# design.net
KiCad netlist of a schematic drawn in EasyEDA Pro
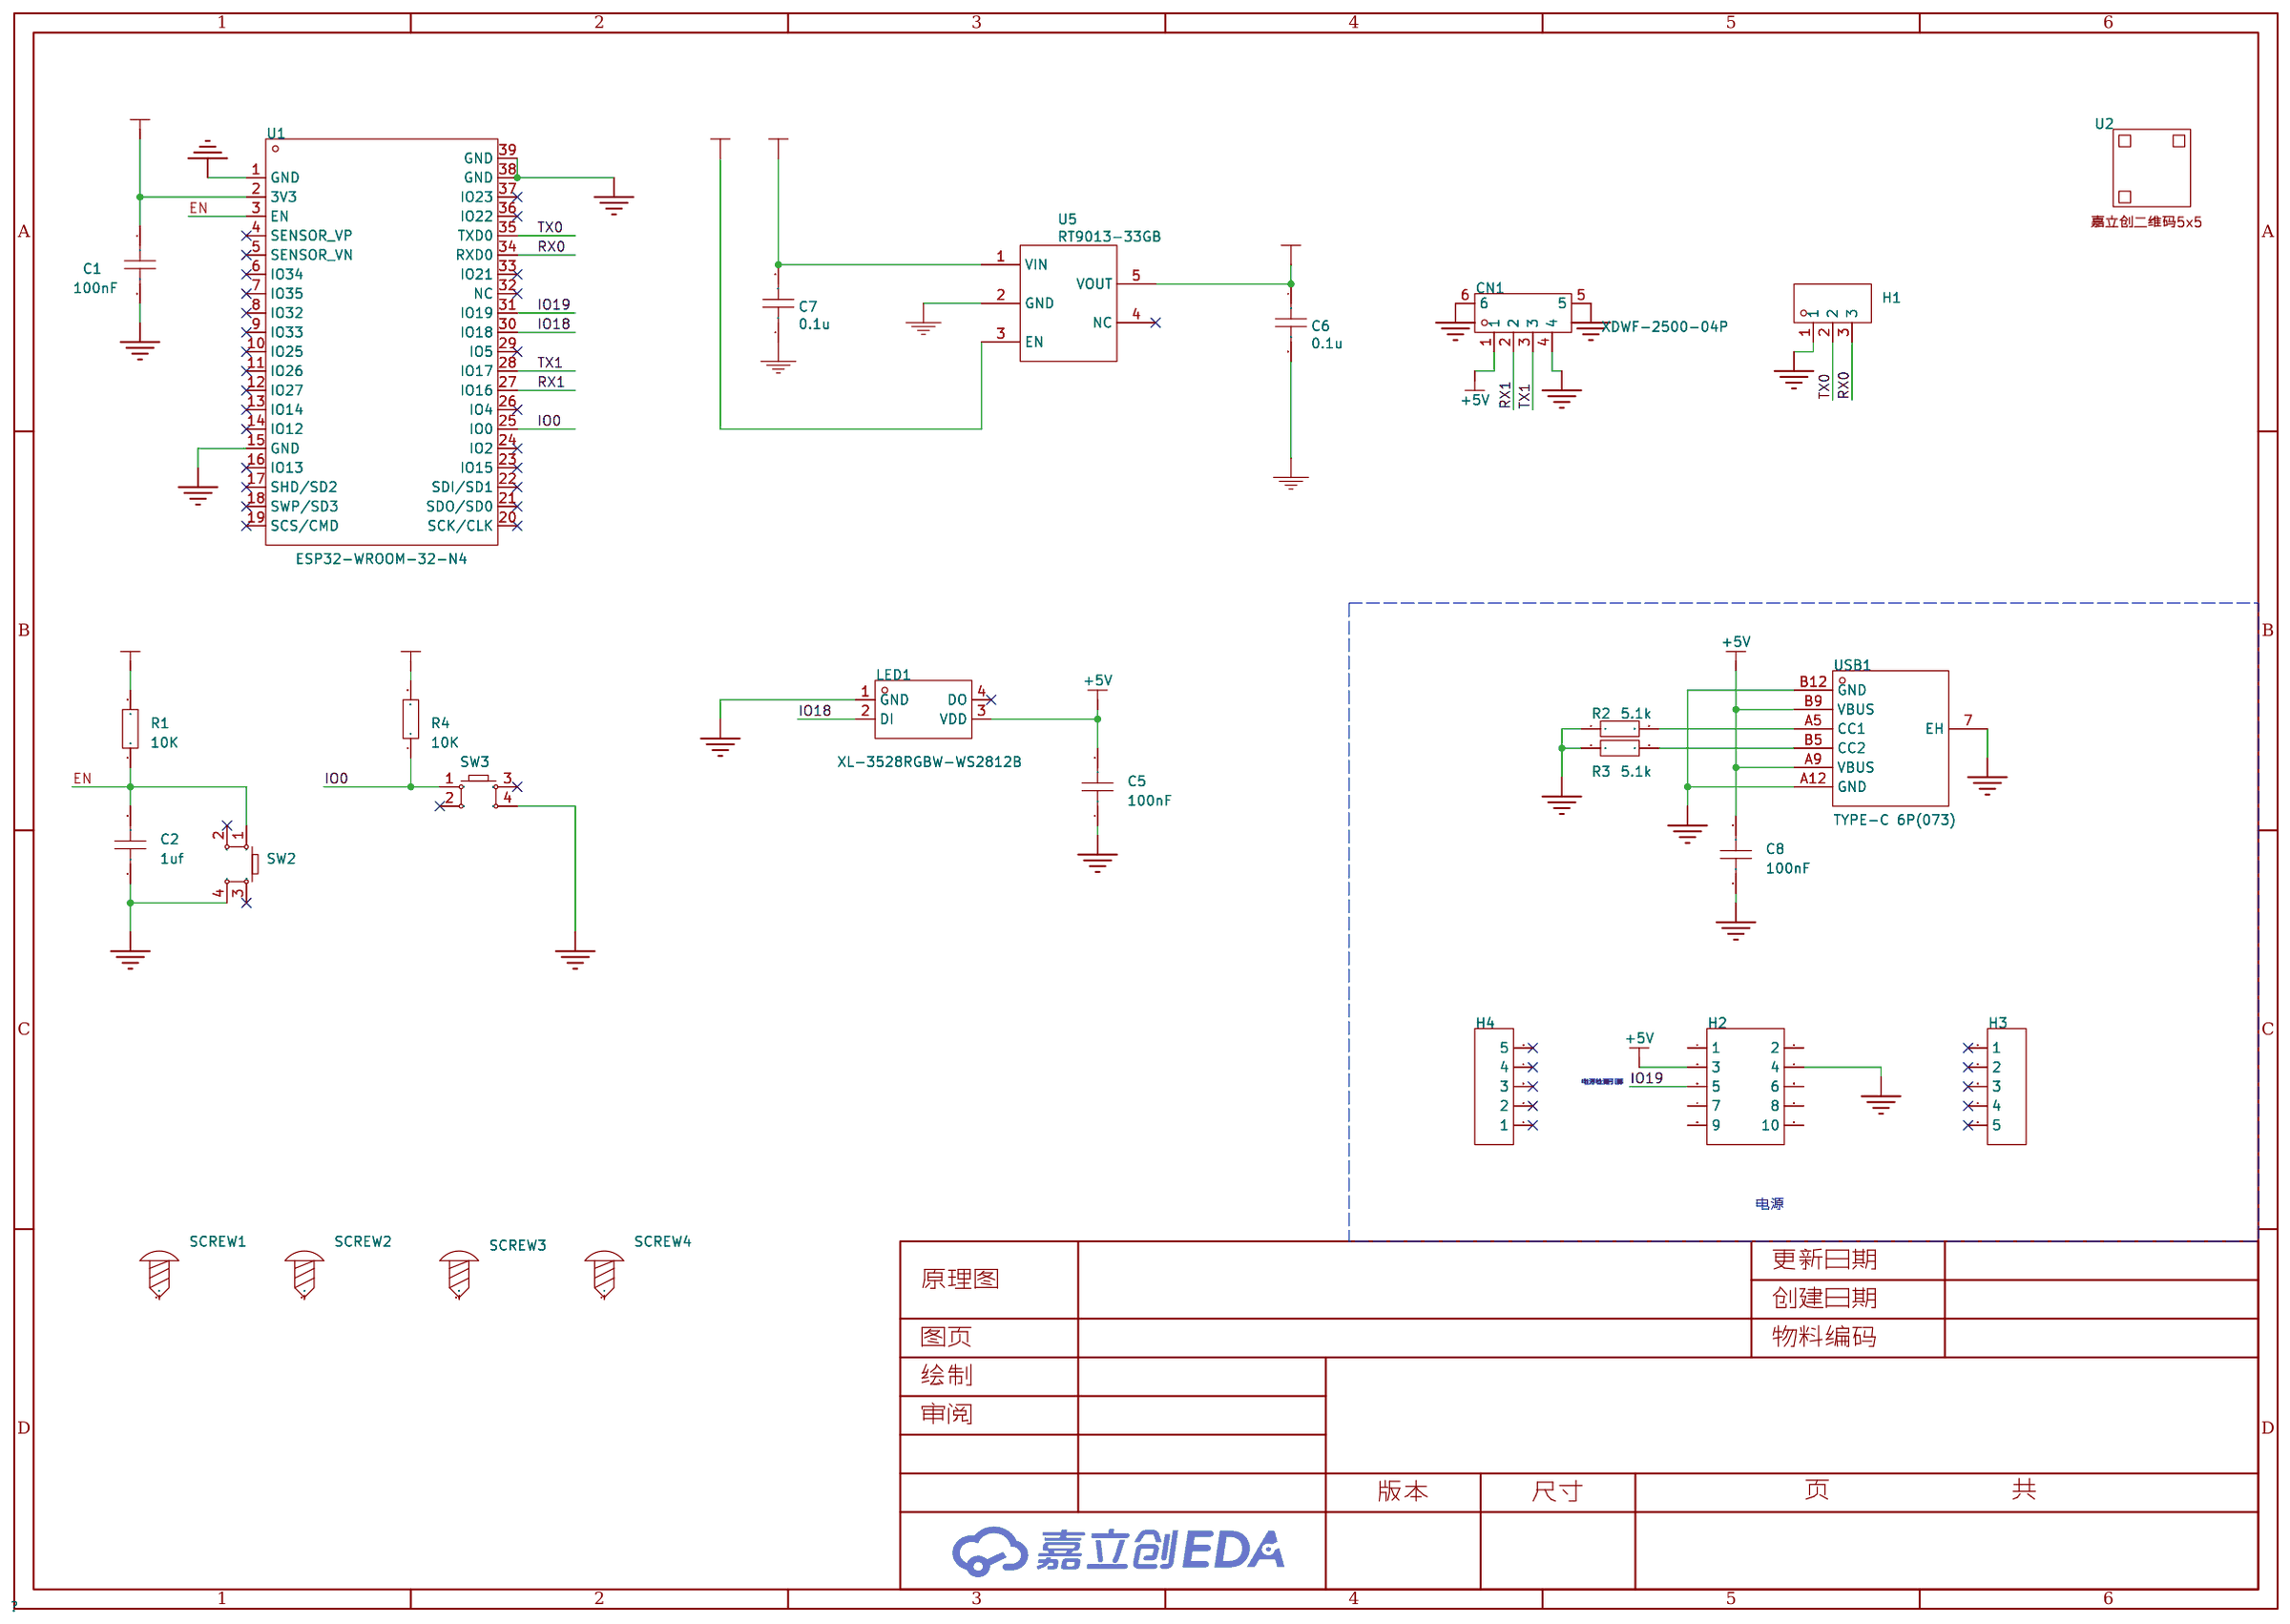
[diagram p0: schematic sheet]

(export (version "E")
  (design (tool "Eeschema 10.0.6"))
  (components
    (comp (ref "C1")
      (value "100nF")
      (footprint "easyedapro:C0603")
      (libsource (lib "easyedapro") (part "CapAcitance"))
    )
    (comp (ref "C2")
      (value "1uf")
      (footprint "easyedapro:C0603")
      (libsource (lib "easyedapro") (part "CapAcitance"))
    )
    (comp (ref "C5")
      (value "100nF")
      (footprint "easyedapro:C0603")
      (libsource (lib "easyedapro") (part "CapAcitance"))
    )
    (comp (ref "C6")
      (value "0.1u")
      (footprint "easyedapro:footprint_8073")
      (libsource (lib "easyedapro") (part "0.1u"))
    )
    (comp (ref "C7")
      (value "0.1u")
      (footprint "easyedapro:footprint_8073")
      (libsource (lib "easyedapro") (part "0.1u"))
    )
    (comp (ref "C8")
      (value "100nF")
      (footprint "easyedapro:C0603")
      (libsource (lib "easyedapro") (part "CapAcitance"))
    )
    (comp (ref "CN1")
      (value "XDWF-2500-04P")
      (footprint "easyedapro:CONN-SMD_4P-P2.50_XDWF-2500-04P")
      (description "间距:2.54mm;安装方式:卧贴;参考系列:XH;总PIN数:4P;额定电流:4A;工作温度范围:-40°C~+85°C;")
      (fields (field (name "Manufacturer") "LX(连欣科技)"))
      (libsource (lib "easyedapro") (part "XDWF-2500-04P"))
    )
    (comp (ref "H1")
      (value "~")
      (footprint "easyedapro:HDR-TH_3P-P2.54-V-M")
      (libsource (lib "easyedapro") (part "PZ254V-11-03P_C2937625"))
    )
    (comp (ref "H2")
      (value "~")
      (footprint "easyedapro:HDR-TH_10P-P2.54-V-F-R2-C5-S2.54")
      (libsource (lib "easyedapro") (part "HDR-F-2.54_2x5"))
    )
    (comp (ref "H3")
      (value "~")
      (footprint "easyedapro:HDR-TH_5P-P2.54-V-F")
      (libsource (lib "easyedapro") (part "Header-Female-2.54_1x5"))
    )
    (comp (ref "H4")
      (value "~")
      (footprint "easyedapro:HDR-TH_5P-P2.54-V-F")
      (libsource (lib "easyedapro") (part "Header-Female-2.54_1x5"))
    )
    (comp (ref "LED1")
      (value "XL-3528RGBW-WS2812B")
      (footprint "easyedapro:LED-SMD_4P-L3.5-W2.8-BR-1")
      (description "3528 七彩幻彩雾状 ws2812B 内置驱动IC")
      (fields (field (name "Manufacturer") "XINGLIGHT(成兴光)"))
      (libsource (lib "easyedapro") (part "XL-3528RGBW-WS2812B"))
    )
    (comp (ref "R1") (value "10K") (footprint "easyedapro:R0603") (libsource (lib "easyedapro") (part "电阻")))
    (comp (ref "R2") (value "5.1k") (footprint "easyedapro:R0603") (libsource (lib "easyedapro") (part "电阻")))
    (comp (ref "R3") (value "5.1k") (footprint "easyedapro:R0603") (libsource (lib "easyedapro") (part "电阻")))
    (comp (ref "R4") (value "10K") (footprint "easyedapro:R0603") (libsource (lib "easyedapro") (part "电阻")))
    (comp (ref "SCREW1")
      (value "~")
      (footprint "easyedapro:M3螺丝")
      (libsource (lib "easyedapro") (part "螺丝孔"))
    )
    (comp (ref "SCREW2")
      (value "~")
      (footprint "easyedapro:M3螺丝")
      (libsource (lib "easyedapro") (part "螺丝孔"))
    )
    (comp (ref "SCREW3")
      (value "~")
      (footprint "easyedapro:M3螺丝")
      (libsource (lib "easyedapro") (part "螺丝孔"))
    )
    (comp (ref "SCREW4")
      (value "~")
      (footprint "easyedapro:M3螺丝")
      (libsource (lib "easyedapro") (part "螺丝孔"))
    )
    (comp (ref "SW2")
      (value "~")
      (footprint "easyedapro:SW-TH_4P-L6.0-W6.0-P4.50-LS6.5")
      (libsource (lib "easyedapro") (part "轻触按键"))
    )
    (comp (ref "SW3")
      (value "~")
      (footprint "easyedapro:SW-TH_4P-L6.0-W6.0-P4.50-LS6.5")
      (libsource (lib "easyedapro") (part "轻触按键"))
    )
    (comp (ref "U1")
      (value "ESP32-WROOM-32-N4")
      (footprint "easyedapro:WIFIM-SMD_ESP32-WROOM-32-N4")
      (description "WiFi+蓝牙4.2+双核CPU,ESP32")
      (fields (field (name "Manufacturer") "ESPRESSIF(乐鑫)"))
      (libsource (lib "easyedapro") (part "ESP32-WROOM-32"))
    )
    (comp (ref "U2")
      (value "~")
      (footprint "easyedapro:JLC-QRCODE-5x5")
      (libsource (lib "easyedapro") (part "嘉立创二维码5x5"))
    )
    (comp (ref "U5")
      (value "RT9013-33GB")
      (footprint "easyedapro:footprint_ad08")
      (fields (field (name "Manufacturer") "RICHTEK(立锜)"))
      (libsource (lib "easyedapro") (part "RT9013-33GB"))
    )
    (comp (ref "USB1")
      (value "TYPE-C 6P(073)")
      (footprint "easyedapro:TYPE-C-SMD_TYPE-C-6P_5")
      (description "连接器类型:Type-C;标准:-;公母:母;端口数量:1;触点数量:6P;安装方式:卧贴;额定电流 - 电源:5A;工作温度范围:-25°C~+85°C;")
      (fields (field (name "Manufacturer") "SHOU HAN(首韩)"))
      (libsource (lib "easyedapro") (part "TYPE-C 6P(073)"))
    )
  )
  (nets
    (net (code "1") (name "+5V") (class "Default")
      (node (ref "C5") (pin "2") (pinfunction "2_2") (pintype "input"))
      (node (ref "C7") (pin "2") (pinfunction "2_2") (pintype "unspecified"))
      (node (ref "C8") (pin "2") (pinfunction "2_2") (pintype "input"))
      (node (ref "CN1") (pin "1") (pinfunction "1_1") (pintype "unspecified"))
      (node (ref "H2") (pin "3") (pinfunction "3_3") (pintype "input"))
      (node (ref "LED1") (pin "3") (pinfunction "VDD_3") (pintype "unspecified"))
      (node (ref "U5") (pin "1") (pinfunction "VIN_1") (pintype "unspecified"))
      (node (ref "U5") (pin "3") (pinfunction "EN_3") (pintype "unspecified"))
      (node (ref "USB1") (pin "A9") (pinfunction "VBUS_A9") (pintype "unspecified"))
      (node (ref "USB1") (pin "B9") (pinfunction "VBUS_B9") (pintype "unspecified"))
    )
    (net (code "2") (name "/EN") (class "Default")
      (node (ref "C2") (pin "2") (pinfunction "2_2") (pintype "input"))
      (node (ref "R1") (pin "1") (pinfunction "1_1") (pintype "input"))
      (node (ref "SW2") (pin "1") (pinfunction "1_1") (pintype "input"))
      (node (ref "U1") (pin "3") (pinfunction "EN_3") (pintype "unspecified"))
    )
    (net (code "3") (name "/IO0") (class "Default")
      (node (ref "R4") (pin "1") (pinfunction "1_1") (pintype "input"))
      (node (ref "SW3") (pin "1") (pinfunction "1_1") (pintype "input"))
      (node (ref "U1") (pin "25") (pinfunction "IO0_25") (pintype "unspecified"))
    )
    (net (code "4") (name "/IO18") (class "Default")
      (node (ref "LED1") (pin "2") (pinfunction "DI_2") (pintype "unspecified"))
      (node (ref "U1") (pin "30") (pinfunction "IO18_30") (pintype "unspecified"))
    )
    (net (code "5") (name "/IO19") (class "Default")
      (node (ref "H2") (pin "5") (pinfunction "5_5") (pintype "input"))
      (node (ref "U1") (pin "31") (pinfunction "IO19_31") (pintype "unspecified"))
    )
    (net (code "6") (name "/RX0") (class "Default")
      (node (ref "H1") (pin "3") (pinfunction "3_3") (pintype "input"))
      (node (ref "U1") (pin "34") (pinfunction "RXD0_34") (pintype "unspecified"))
    )
    (net (code "7") (name "/RX1") (class "Default")
      (node (ref "CN1") (pin "2") (pinfunction "2_2") (pintype "unspecified"))
      (node (ref "U1") (pin "27") (pinfunction "IO16_27") (pintype "unspecified"))
    )
    (net (code "8") (name "/TX0") (class "Default")
      (node (ref "H1") (pin "2") (pinfunction "2_2") (pintype "input"))
      (node (ref "U1") (pin "35") (pinfunction "TXD0_35") (pintype "unspecified"))
    )
    (net (code "9") (name "/TX1") (class "Default")
      (node (ref "CN1") (pin "3") (pinfunction "3_3") (pintype "unspecified"))
      (node (ref "U1") (pin "28") (pinfunction "IO17_28") (pintype "unspecified"))
    )
    (net (code "10") (name "3.3V") (class "Default")
      (node (ref "C1") (pin "1") (pinfunction "1_1") (pintype "input"))
      (node (ref "C6") (pin "1") (pinfunction "1_1") (pintype "unspecified"))
      (node (ref "R1") (pin "2") (pinfunction "2_2") (pintype "input"))
      (node (ref "R4") (pin "2") (pinfunction "2_2") (pintype "input"))
      (node (ref "U1") (pin "2") (pinfunction "3V3_2") (pintype "unspecified"))
      (node (ref "U5") (pin "5") (pinfunction "VOUT_5") (pintype "unspecified"))
    )
    (net (code "11") (name "GND") (class "Default")
      (node (ref "C1") (pin "2") (pinfunction "2_2") (pintype "input"))
      (node (ref "C2") (pin "1") (pinfunction "1_1") (pintype "input"))
      (node (ref "C5") (pin "1") (pinfunction "1_1") (pintype "input"))
      (node (ref "C6") (pin "2") (pinfunction "2_2") (pintype "unspecified"))
      (node (ref "C7") (pin "1") (pinfunction "1_1") (pintype "unspecified"))
      (node (ref "C8") (pin "1") (pinfunction "1_1") (pintype "input"))
      (node (ref "CN1") (pin "4") (pinfunction "4_4") (pintype "unspecified"))
      (node (ref "CN1") (pin "5") (pinfunction "5_5") (pintype "unspecified"))
      (node (ref "CN1") (pin "6") (pinfunction "6_6") (pintype "unspecified"))
      (node (ref "H1") (pin "1") (pinfunction "1_1") (pintype "input"))
      (node (ref "H2") (pin "4") (pinfunction "4_4") (pintype "input"))
      (node (ref "LED1") (pin "1") (pinfunction "GND_1") (pintype "unspecified"))
      (node (ref "R2") (pin "1") (pinfunction "1_1") (pintype "input"))
      (node (ref "R3") (pin "1") (pinfunction "1_1") (pintype "input"))
      (node (ref "SW2") (pin "4") (pinfunction "4_4") (pintype "input"))
      (node (ref "SW3") (pin "4") (pinfunction "4_4") (pintype "input"))
      (node (ref "U1") (pin "1") (pinfunction "GND_1") (pintype "unspecified"))
      (node (ref "U1") (pin "15") (pinfunction "GND_15") (pintype "unspecified"))
      (node (ref "U1") (pin "38") (pinfunction "GND_38") (pintype "unspecified"))
      (node (ref "U1") (pin "39") (pinfunction "GND_39") (pintype "unspecified"))
      (node (ref "U5") (pin "2") (pinfunction "GND_2") (pintype "unspecified"))
      (node (ref "USB1") (pin "7") (pinfunction "EH_7") (pintype "unspecified"))
      (node (ref "USB1") (pin "A12") (pinfunction "GND_A12") (pintype "unspecified"))
      (node (ref "USB1") (pin "B12") (pinfunction "GND_B12") (pintype "unspecified"))
    )
    (net (code "12") (name "Net-(USB1-CC1)") (class "Default")
      (node (ref "R2") (pin "2") (pinfunction "2_2") (pintype "input"))
      (node (ref "USB1") (pin "A5") (pinfunction "CC1_A5") (pintype "unspecified"))
    )
    (net (code "13") (name "Net-(USB1-CC2)") (class "Default")
      (node (ref "R3") (pin "2") (pinfunction "2_2") (pintype "input"))
      (node (ref "USB1") (pin "B5") (pinfunction "CC2_B5") (pintype "unspecified"))
    )
    (net (code "14") (name "unconnected-(H2-Pad1)") (class "Default")
      (node (ref "H2") (pin "1") (pinfunction "1_1") (pintype "input"))
    )
    (net (code "15") (name "unconnected-(H2-Pad2)") (class "Default")
      (node (ref "H2") (pin "2") (pinfunction "2_2") (pintype "input"))
    )
    (net (code "16") (name "unconnected-(H2-Pad6)") (class "Default")
      (node (ref "H2") (pin "6") (pinfunction "6_6") (pintype "input"))
    )
    (net (code "17") (name "unconnected-(H2-Pad7)") (class "Default")
      (node (ref "H2") (pin "7") (pinfunction "7_7") (pintype "input"))
    )
    (net (code "18") (name "unconnected-(H2-Pad8)") (class "Default")
      (node (ref "H2") (pin "8") (pinfunction "8_8") (pintype "input"))
    )
    (net (code "19") (name "unconnected-(H2-Pad9)") (class "Default")
      (node (ref "H2") (pin "9") (pinfunction "9_9") (pintype "input"))
    )
    (net (code "20") (name "unconnected-(H2-Pad10)") (class "Default")
      (node (ref "H2") (pin "10") (pinfunction "10_10") (pintype "input"))
    )
    (net (code "21") (name "unconnected-(H3-Pad1)") (class "Default")
      (node (ref "H3") (pin "1") (pinfunction "1_1") (pintype "input+no_connect"))
    )
    (net (code "22") (name "unconnected-(H3-Pad2)") (class "Default")
      (node (ref "H3") (pin "2") (pinfunction "2_2") (pintype "input+no_connect"))
    )
    (net (code "23") (name "unconnected-(H3-Pad3)") (class "Default")
      (node (ref "H3") (pin "3") (pinfunction "3_3") (pintype "input+no_connect"))
    )
    (net (code "24") (name "unconnected-(H3-Pad4)") (class "Default")
      (node (ref "H3") (pin "4") (pinfunction "4_4") (pintype "input+no_connect"))
    )
    (net (code "25") (name "unconnected-(H3-Pad5)") (class "Default")
      (node (ref "H3") (pin "5") (pinfunction "5_5") (pintype "input+no_connect"))
    )
    (net (code "26") (name "unconnected-(H4-Pad1)") (class "Default")
      (node (ref "H4") (pin "1") (pinfunction "1_1") (pintype "input+no_connect"))
    )
    (net (code "27") (name "unconnected-(H4-Pad2)") (class "Default")
      (node (ref "H4") (pin "2") (pinfunction "2_2") (pintype "input+no_connect"))
    )
    (net (code "28") (name "unconnected-(H4-Pad3)") (class "Default")
      (node (ref "H4") (pin "3") (pinfunction "3_3") (pintype "input+no_connect"))
    )
    (net (code "29") (name "unconnected-(H4-Pad4)") (class "Default")
      (node (ref "H4") (pin "4") (pinfunction "4_4") (pintype "input+no_connect"))
    )
    (net (code "30") (name "unconnected-(H4-Pad5)") (class "Default")
      (node (ref "H4") (pin "5") (pinfunction "5_5") (pintype "input+no_connect"))
    )
    (net (code "31") (name "unconnected-(LED1-DO-Pad4)") (class "Default")
      (node (ref "LED1") (pin "4") (pinfunction "DO_4") (pintype "unspecified+no_connect"))
    )
    (net (code "32") (name "unconnected-(SCREW1-Pad1)") (class "Default")
      (node (ref "SCREW1") (pin "1") (pinfunction "1_1") (pintype "input"))
    )
    (net (code "33") (name "unconnected-(SCREW2-Pad1)") (class "Default")
      (node (ref "SCREW2") (pin "1") (pinfunction "1_1") (pintype "input"))
    )
    (net (code "34") (name "unconnected-(SCREW3-Pad1)") (class "Default")
      (node (ref "SCREW3") (pin "1") (pinfunction "1_1") (pintype "input"))
    )
    (net (code "35") (name "unconnected-(SCREW4-Pad1)") (class "Default")
      (node (ref "SCREW4") (pin "1") (pinfunction "1_1") (pintype "input"))
    )
    (net (code "36") (name "unconnected-(SW2-Pad2)") (class "Default")
      (node (ref "SW2") (pin "2") (pinfunction "2_2") (pintype "input+no_connect"))
    )
    (net (code "37") (name "unconnected-(SW2-Pad3)") (class "Default")
      (node (ref "SW2") (pin "3") (pinfunction "3_3") (pintype "input+no_connect"))
    )
    (net (code "38") (name "unconnected-(SW3-Pad2)") (class "Default")
      (node (ref "SW3") (pin "2") (pinfunction "2_2") (pintype "input+no_connect"))
    )
    (net (code "39") (name "unconnected-(SW3-Pad3)") (class "Default")
      (node (ref "SW3") (pin "3") (pinfunction "3_3") (pintype "input+no_connect"))
    )
    (net (code "40") (name "unconnected-(U1-IO2-Pad24)") (class "Default")
      (node (ref "U1") (pin "24") (pinfunction "IO2_24") (pintype "unspecified+no_connect"))
    )
    (net (code "41") (name "unconnected-(U1-IO4-Pad26)") (class "Default")
      (node (ref "U1") (pin "26") (pinfunction "IO4_26") (pintype "unspecified+no_connect"))
    )
    (net (code "42") (name "unconnected-(U1-IO5-Pad29)") (class "Default")
      (node (ref "U1") (pin "29") (pinfunction "IO5_29") (pintype "unspecified+no_connect"))
    )
    (net (code "43") (name "unconnected-(U1-IO12-Pad14)") (class "Default")
      (node (ref "U1") (pin "14") (pinfunction "IO12_14") (pintype "unspecified+no_connect"))
    )
    (net (code "44") (name "unconnected-(U1-IO13-Pad16)") (class "Default")
      (node (ref "U1") (pin "16") (pinfunction "IO13_16") (pintype "unspecified+no_connect"))
    )
    (net (code "45") (name "unconnected-(U1-IO14-Pad13)") (class "Default")
      (node (ref "U1") (pin "13") (pinfunction "IO14_13") (pintype "unspecified+no_connect"))
    )
    (net (code "46") (name "unconnected-(U1-IO15-Pad23)") (class "Default")
      (node (ref "U1") (pin "23") (pinfunction "IO15_23") (pintype "unspecified+no_connect"))
    )
    (net (code "47") (name "unconnected-(U1-IO21-Pad33)") (class "Default")
      (node (ref "U1") (pin "33") (pinfunction "IO21_33") (pintype "unspecified+no_connect"))
    )
    (net (code "48") (name "unconnected-(U1-IO22-Pad36)") (class "Default")
      (node (ref "U1") (pin "36") (pinfunction "IO22_36") (pintype "unspecified+no_connect"))
    )
    (net (code "49") (name "unconnected-(U1-IO23-Pad37)") (class "Default")
      (node (ref "U1") (pin "37") (pinfunction "IO23_37") (pintype "unspecified+no_connect"))
    )
    (net (code "50") (name "unconnected-(U1-IO25-Pad10)") (class "Default")
      (node (ref "U1") (pin "10") (pinfunction "IO25_10") (pintype "unspecified+no_connect"))
    )
    (net (code "51") (name "unconnected-(U1-IO26-Pad11)") (class "Default")
      (node (ref "U1") (pin "11") (pinfunction "IO26_11") (pintype "unspecified+no_connect"))
    )
    (net (code "52") (name "unconnected-(U1-IO27-Pad12)") (class "Default")
      (node (ref "U1") (pin "12") (pinfunction "IO27_12") (pintype "unspecified+no_connect"))
    )
    (net (code "53") (name "unconnected-(U1-IO32-Pad8)") (class "Default")
      (node (ref "U1") (pin "8") (pinfunction "IO32_8") (pintype "unspecified+no_connect"))
    )
    (net (code "54") (name "unconnected-(U1-IO33-Pad9)") (class "Default")
      (node (ref "U1") (pin "9") (pinfunction "IO33_9") (pintype "unspecified+no_connect"))
    )
    (net (code "55") (name "unconnected-(U1-IO34-Pad6)") (class "Default")
      (node (ref "U1") (pin "6") (pinfunction "IO34_6") (pintype "unspecified+no_connect"))
    )
    (net (code "56") (name "unconnected-(U1-IO35-Pad7)") (class "Default")
      (node (ref "U1") (pin "7") (pinfunction "IO35_7") (pintype "unspecified+no_connect"))
    )
    (net (code "57") (name "unconnected-(U1-NC-Pad32)") (class "Default")
      (node (ref "U1") (pin "32") (pinfunction "NC_32") (pintype "unspecified+no_connect"))
    )
    (net (code "58") (name "unconnected-(U1-SCK{slash}CLK-Pad20)") (class "Default")
      (node (ref "U1") (pin "20") (pinfunction "SCK/CLK_20") (pintype "unspecified+no_connect"))
    )
    (net (code "59") (name "unconnected-(U1-SCS{slash}CMD-Pad19)") (class "Default")
      (node (ref "U1") (pin "19") (pinfunction "SCS/CMD_19") (pintype "unspecified+no_connect"))
    )
    (net (code "60") (name "unconnected-(U1-SDI{slash}SD1-Pad22)") (class "Default")
      (node (ref "U1") (pin "22") (pinfunction "SDI/SD1_22") (pintype "unspecified+no_connect"))
    )
    (net (code "61") (name "unconnected-(U1-SDO{slash}SD0-Pad21)") (class "Default")
      (node (ref "U1") (pin "21") (pinfunction "SDO/SD0_21") (pintype "unspecified+no_connect"))
    )
    (net (code "62") (name "unconnected-(U1-SENSOR_VN-Pad5)") (class "Default")
      (node (ref "U1") (pin "5") (pinfunction "SENSOR_VN_5") (pintype "unspecified+no_connect"))
    )
    (net (code "63") (name "unconnected-(U1-SENSOR_VP-Pad4)") (class "Default")
      (node (ref "U1") (pin "4") (pinfunction "SENSOR_VP_4") (pintype "unspecified+no_connect"))
    )
    (net (code "64") (name "unconnected-(U1-SHD{slash}SD2-Pad17)") (class "Default")
      (node (ref "U1") (pin "17") (pinfunction "SHD/SD2_17") (pintype "unspecified+no_connect"))
    )
    (net (code "65") (name "unconnected-(U1-SWP{slash}SD3-Pad18)") (class "Default")
      (node (ref "U1") (pin "18") (pinfunction "SWP/SD3_18") (pintype "unspecified+no_connect"))
    )
    (net (code "66") (name "unconnected-(U5-NC-Pad4)") (class "Default")
      (node (ref "U5") (pin "4") (pinfunction "NC_4") (pintype "unspecified+no_connect"))
    )
  )
)
